# 24x16_RGB_Bottom.net
KiCad netlist of a schematic drawn in EAGLE
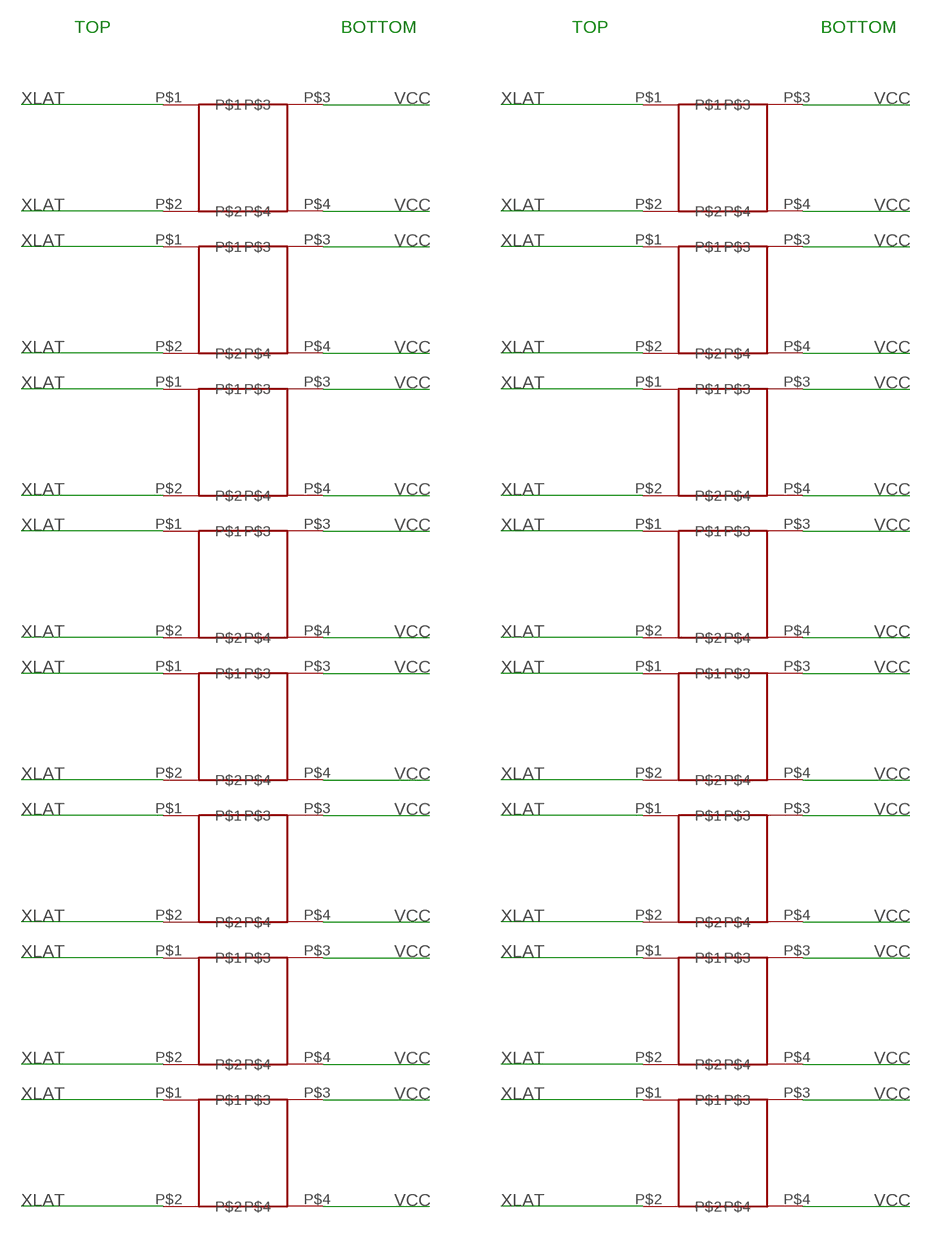
[diagram p0: schematic, sheet 1]
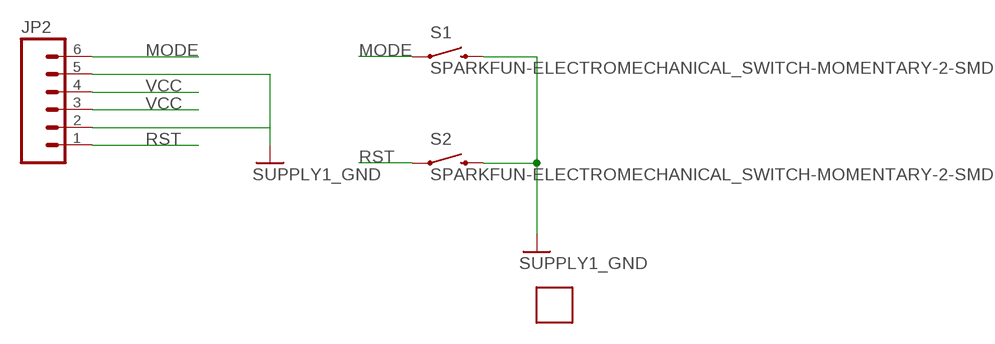
[diagram p1: schematic, sheet 2]

(export (version "E")
  (design (tool "Eeschema 10.0.6"))
  (components
    (comp (ref "SLOT1")
      (value "SLOT")
      (footprint "eagle-import:SLOT")
      (libsource (lib "eagle-import") (part "SLOT"))
    )
    (comp (ref "SLOT2")
      (value "SLOT")
      (footprint "eagle-import:SLOT")
      (libsource (lib "eagle-import") (part "SLOT"))
    )
    (comp (ref "SLOT3")
      (value "SLOT")
      (footprint "eagle-import:SLOT")
      (libsource (lib "eagle-import") (part "SLOT"))
    )
    (comp (ref "SLOT4")
      (value "SLOT")
      (footprint "eagle-import:SLOT")
      (libsource (lib "eagle-import") (part "SLOT"))
    )
    (comp (ref "SLOT5")
      (value "SLOT")
      (footprint "eagle-import:SLOT")
      (libsource (lib "eagle-import") (part "SLOT"))
    )
    (comp (ref "SLOT6")
      (value "SLOT")
      (footprint "eagle-import:SLOT")
      (libsource (lib "eagle-import") (part "SLOT"))
    )
    (comp (ref "SLOT7")
      (value "SLOT")
      (footprint "eagle-import:SLOT")
      (libsource (lib "eagle-import") (part "SLOT"))
    )
    (comp (ref "SLOT8")
      (value "SLOT")
      (footprint "eagle-import:SLOT")
      (libsource (lib "eagle-import") (part "SLOT"))
    )
    (comp (ref "SLOT9")
      (value "SLOT")
      (footprint "eagle-import:SLOT")
      (libsource (lib "eagle-import") (part "SLOT"))
    )
    (comp (ref "SLOT10")
      (value "SLOT")
      (footprint "eagle-import:SLOT")
      (libsource (lib "eagle-import") (part "SLOT"))
    )
    (comp (ref "SLOT11")
      (value "SLOT")
      (footprint "eagle-import:SLOT")
      (libsource (lib "eagle-import") (part "SLOT"))
    )
    (comp (ref "SLOT12")
      (value "SLOT")
      (footprint "eagle-import:SLOT")
      (libsource (lib "eagle-import") (part "SLOT"))
    )
    (comp (ref "SLOT13")
      (value "SLOT")
      (footprint "eagle-import:SLOT")
      (libsource (lib "eagle-import") (part "SLOT"))
    )
    (comp (ref "SLOT14")
      (value "SLOT")
      (footprint "eagle-import:SLOT")
      (libsource (lib "eagle-import") (part "SLOT"))
    )
    (comp (ref "SLOT15")
      (value "SLOT")
      (footprint "eagle-import:SLOT")
      (libsource (lib "eagle-import") (part "SLOT"))
    )
    (comp (ref "SLOT16")
      (value "SLOT")
      (footprint "eagle-import:SLOT")
      (libsource (lib "eagle-import") (part "SLOT"))
    )
    (comp (ref "JP2")
      (value "M06SIP")
      (footprint "eagle-import:1X06")
      (libsource (lib "eagle-import") (part "M06SIP"))
    )
    (comp (ref "S1")
      (value "SPARKFUN-ELECTROMECHANICAL_SWITCH-MOMENTARY-2-SMD-1101NE")
      (footprint "eagle-import:SPARKFUN-ELECTROMECHANICAL_TACTILE-SWITCH-1101NE")
      (libsource (lib "eagle-import") (part "SPARKFUN-ELECTROMECHANICAL_SWITCH-MOMENTARY-2-SMD-1101NE"))
    )
    (comp (ref "S2")
      (value "SPARKFUN-ELECTROMECHANICAL_SWITCH-MOMENTARY-2-SMD-1101NE")
      (footprint "eagle-import:SPARKFUN-ELECTROMECHANICAL_TACTILE-SWITCH-1101NE")
      (libsource (lib "eagle-import") (part "SPARKFUN-ELECTROMECHANICAL_SWITCH-MOMENTARY-2-SMD-1101NE"))
    )
    (comp (ref "U$1")
      (value "DC_PWR")
      (footprint "eagle-import:DC_2.1")
      (libsource (lib "eagle-import") (part "DC_PWR"))
    )
  )
  (nets
    (net (code "1") (name "GND") (class "Default")
      (node (ref "JP2") (pin "2") (pinfunction "2_2") (pintype "passive"))
      (node (ref "JP2") (pin "5") (pinfunction "5_5") (pintype "passive"))
      (node (ref "S1") (pin "P$2") (pinfunction "2_P$2") (pintype "passive"))
      (node (ref "S2") (pin "P$2") (pinfunction "2_P$2") (pintype "passive"))
    )
    (net (code "2") (name "MODE") (class "Default")
      (node (ref "JP2") (pin "6") (pinfunction "6_6") (pintype "passive"))
      (node (ref "S1") (pin "P$1") (pinfunction "1_P$1") (pintype "passive"))
    )
    (net (code "3") (name "RST") (class "Default")
      (node (ref "JP2") (pin "1") (pinfunction "1_1") (pintype "passive"))
      (node (ref "S2") (pin "P$1") (pinfunction "1_P$1") (pintype "passive"))
    )
    (net (code "4") (name "VCC") (class "Default")
      (node (ref "JP2") (pin "3") (pinfunction "3_3") (pintype "passive"))
      (node (ref "JP2") (pin "4") (pinfunction "4_4") (pintype "passive"))
      (node (ref "SLOT1") (pin "P$3") (pinfunction "P$3_P$3") (pintype "bidirectional"))
      (node (ref "SLOT1") (pin "P$4") (pinfunction "P$4_P$4") (pintype "bidirectional"))
      (node (ref "SLOT10") (pin "P$3") (pinfunction "P$3_P$3") (pintype "bidirectional"))
      (node (ref "SLOT10") (pin "P$4") (pinfunction "P$4_P$4") (pintype "bidirectional"))
      (node (ref "SLOT11") (pin "P$3") (pinfunction "P$3_P$3") (pintype "bidirectional"))
      (node (ref "SLOT11") (pin "P$4") (pinfunction "P$4_P$4") (pintype "bidirectional"))
      (node (ref "SLOT12") (pin "P$3") (pinfunction "P$3_P$3") (pintype "bidirectional"))
      (node (ref "SLOT12") (pin "P$4") (pinfunction "P$4_P$4") (pintype "bidirectional"))
      (node (ref "SLOT13") (pin "P$3") (pinfunction "P$3_P$3") (pintype "bidirectional"))
      (node (ref "SLOT13") (pin "P$4") (pinfunction "P$4_P$4") (pintype "bidirectional"))
      (node (ref "SLOT14") (pin "P$3") (pinfunction "P$3_P$3") (pintype "bidirectional"))
      (node (ref "SLOT14") (pin "P$4") (pinfunction "P$4_P$4") (pintype "bidirectional"))
      (node (ref "SLOT15") (pin "P$3") (pinfunction "P$3_P$3") (pintype "bidirectional"))
      (node (ref "SLOT15") (pin "P$4") (pinfunction "P$4_P$4") (pintype "bidirectional"))
      (node (ref "SLOT16") (pin "P$3") (pinfunction "P$3_P$3") (pintype "bidirectional"))
      (node (ref "SLOT16") (pin "P$4") (pinfunction "P$4_P$4") (pintype "bidirectional"))
      (node (ref "SLOT2") (pin "P$3") (pinfunction "P$3_P$3") (pintype "bidirectional"))
      (node (ref "SLOT2") (pin "P$4") (pinfunction "P$4_P$4") (pintype "bidirectional"))
      (node (ref "SLOT3") (pin "P$3") (pinfunction "P$3_P$3") (pintype "bidirectional"))
      (node (ref "SLOT3") (pin "P$4") (pinfunction "P$4_P$4") (pintype "bidirectional"))
      (node (ref "SLOT4") (pin "P$3") (pinfunction "P$3_P$3") (pintype "bidirectional"))
      (node (ref "SLOT4") (pin "P$4") (pinfunction "P$4_P$4") (pintype "bidirectional"))
      (node (ref "SLOT5") (pin "P$3") (pinfunction "P$3_P$3") (pintype "bidirectional"))
      (node (ref "SLOT5") (pin "P$4") (pinfunction "P$4_P$4") (pintype "bidirectional"))
      (node (ref "SLOT6") (pin "P$3") (pinfunction "P$3_P$3") (pintype "bidirectional"))
      (node (ref "SLOT6") (pin "P$4") (pinfunction "P$4_P$4") (pintype "bidirectional"))
      (node (ref "SLOT7") (pin "P$3") (pinfunction "P$3_P$3") (pintype "bidirectional"))
      (node (ref "SLOT7") (pin "P$4") (pinfunction "P$4_P$4") (pintype "bidirectional"))
      (node (ref "SLOT8") (pin "P$3") (pinfunction "P$3_P$3") (pintype "bidirectional"))
      (node (ref "SLOT8") (pin "P$4") (pinfunction "P$4_P$4") (pintype "bidirectional"))
      (node (ref "SLOT9") (pin "P$3") (pinfunction "P$3_P$3") (pintype "bidirectional"))
      (node (ref "SLOT9") (pin "P$4") (pinfunction "P$4_P$4") (pintype "bidirectional"))
    )
    (net (code "5") (name "XLAT") (class "Default")
      (node (ref "SLOT1") (pin "P$1") (pinfunction "P$1_P$1") (pintype "bidirectional"))
      (node (ref "SLOT1") (pin "P$2") (pinfunction "P$2_P$2") (pintype "bidirectional"))
      (node (ref "SLOT10") (pin "P$1") (pinfunction "P$1_P$1") (pintype "bidirectional"))
      (node (ref "SLOT10") (pin "P$2") (pinfunction "P$2_P$2") (pintype "bidirectional"))
      (node (ref "SLOT11") (pin "P$1") (pinfunction "P$1_P$1") (pintype "bidirectional"))
      (node (ref "SLOT11") (pin "P$2") (pinfunction "P$2_P$2") (pintype "bidirectional"))
      (node (ref "SLOT12") (pin "P$1") (pinfunction "P$1_P$1") (pintype "bidirectional"))
      (node (ref "SLOT12") (pin "P$2") (pinfunction "P$2_P$2") (pintype "bidirectional"))
      (node (ref "SLOT13") (pin "P$1") (pinfunction "P$1_P$1") (pintype "bidirectional"))
      (node (ref "SLOT13") (pin "P$2") (pinfunction "P$2_P$2") (pintype "bidirectional"))
      (node (ref "SLOT14") (pin "P$1") (pinfunction "P$1_P$1") (pintype "bidirectional"))
      (node (ref "SLOT14") (pin "P$2") (pinfunction "P$2_P$2") (pintype "bidirectional"))
      (node (ref "SLOT15") (pin "P$1") (pinfunction "P$1_P$1") (pintype "bidirectional"))
      (node (ref "SLOT15") (pin "P$2") (pinfunction "P$2_P$2") (pintype "bidirectional"))
      (node (ref "SLOT16") (pin "P$1") (pinfunction "P$1_P$1") (pintype "bidirectional"))
      (node (ref "SLOT16") (pin "P$2") (pinfunction "P$2_P$2") (pintype "bidirectional"))
      (node (ref "SLOT2") (pin "P$1") (pinfunction "P$1_P$1") (pintype "bidirectional"))
      (node (ref "SLOT2") (pin "P$2") (pinfunction "P$2_P$2") (pintype "bidirectional"))
      (node (ref "SLOT3") (pin "P$1") (pinfunction "P$1_P$1") (pintype "bidirectional"))
      (node (ref "SLOT3") (pin "P$2") (pinfunction "P$2_P$2") (pintype "bidirectional"))
      (node (ref "SLOT4") (pin "P$1") (pinfunction "P$1_P$1") (pintype "bidirectional"))
      (node (ref "SLOT4") (pin "P$2") (pinfunction "P$2_P$2") (pintype "bidirectional"))
      (node (ref "SLOT5") (pin "P$1") (pinfunction "P$1_P$1") (pintype "bidirectional"))
      (node (ref "SLOT5") (pin "P$2") (pinfunction "P$2_P$2") (pintype "bidirectional"))
      (node (ref "SLOT6") (pin "P$1") (pinfunction "P$1_P$1") (pintype "bidirectional"))
      (node (ref "SLOT6") (pin "P$2") (pinfunction "P$2_P$2") (pintype "bidirectional"))
      (node (ref "SLOT7") (pin "P$1") (pinfunction "P$1_P$1") (pintype "bidirectional"))
      (node (ref "SLOT7") (pin "P$2") (pinfunction "P$2_P$2") (pintype "bidirectional"))
      (node (ref "SLOT8") (pin "P$1") (pinfunction "P$1_P$1") (pintype "bidirectional"))
      (node (ref "SLOT8") (pin "P$2") (pinfunction "P$2_P$2") (pintype "bidirectional"))
      (node (ref "SLOT9") (pin "P$1") (pinfunction "P$1_P$1") (pintype "bidirectional"))
      (node (ref "SLOT9") (pin "P$2") (pinfunction "P$2_P$2") (pintype "bidirectional"))
    )
  )
)
